# Goldfinger_Connector.net
KiCad netlist of a schematic drawn in Altium Designer
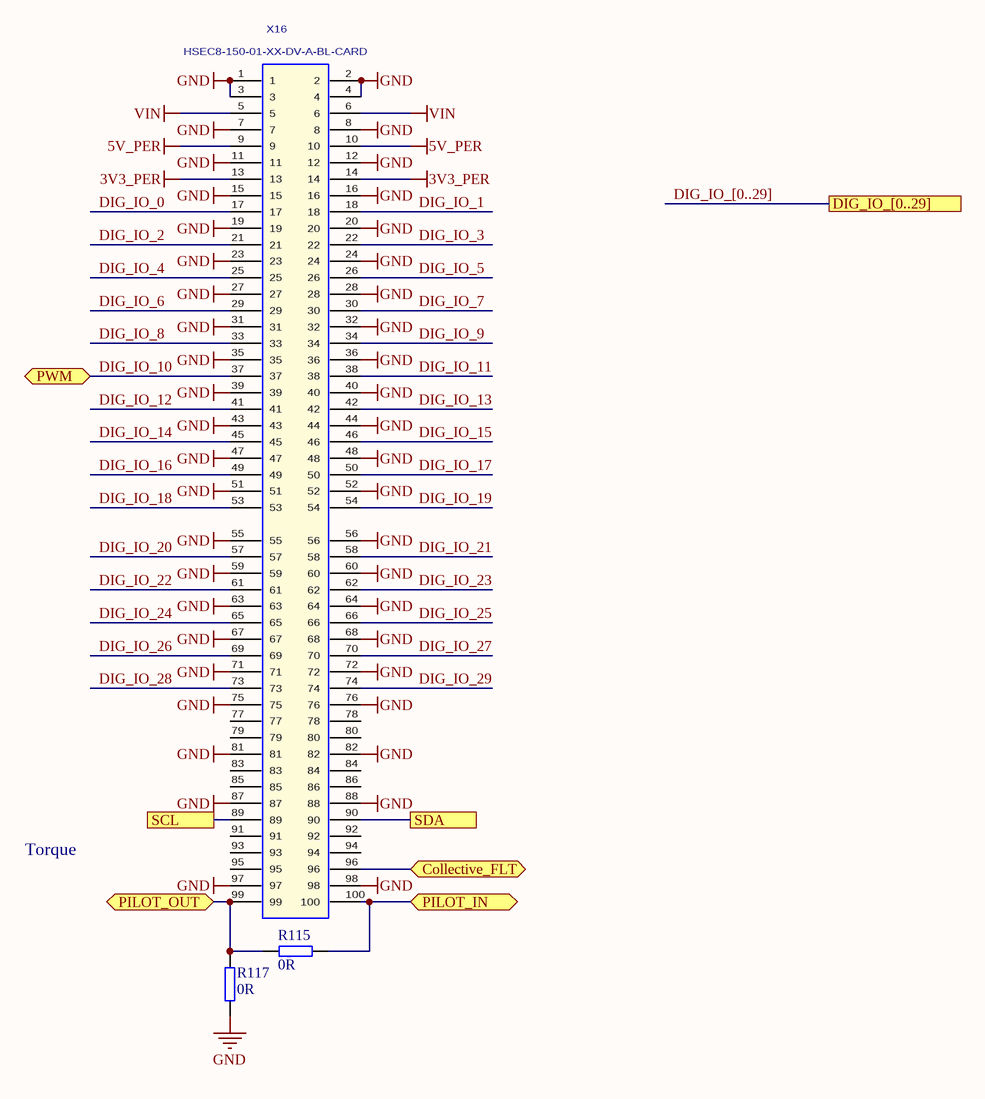
[diagram p0: Goldfinger_Connector.SchDoc]

(export (version "E")
  (design (tool "Eeschema 10.0.6"))
  (components
    (comp (ref "R115")
      (value "0R")
      (footprint "RESC1608X06N")
      (fields (field (name "MF") "Vishay") (field (name "MPN") "CRCW06030000Z0EAC"))
      (libsource (lib "UltraZohm_ADC") (part "R_0603"))
    )
    (comp (ref "R117")
      (value "0R")
      (footprint "RESC1608X06N")
      (fields (field (name "MF") "Vishay") (field (name "MPN") "CRCW06030000Z0EAC"))
      (libsource (lib "UltraZohm_ADC") (part "R_0603"))
    )
    (comp (ref "X16")
      (value "HSEC8-150-01-XX-DV-A-BL-CARD")
      (footprint "HSEC8-150-01-XX-DV-A-BL-CARD")
      (description "Mating Card Layout for HSEC8-150-01-XX-DV-A-BL")
      (fields (field (name "MANUFACTURER") "SAMTEC") (field (name "CREATED") "2018_04_23_AGeiger"))
      (libsource (lib "Samtec") (part "HSEC8-150-01-XX-DV-A-BL-CARD"))
    )
  )
  (nets
    (net (code "1") (name "/Collective_FLT") (class "Default")
      (node (ref "X16") (pin "96") (pinfunction "96_96") (pintype "passive"))
    )
    (net (code "2") (name "/DIG_IO_0") (class "Default")
      (node (ref "X16") (pin "17") (pinfunction "17_17") (pintype "passive"))
    )
    (net (code "3") (name "/DIG_IO_1") (class "Default")
      (node (ref "X16") (pin "18") (pinfunction "18_18") (pintype "passive"))
    )
    (net (code "4") (name "/DIG_IO_2") (class "Default")
      (node (ref "X16") (pin "21") (pinfunction "21_21") (pintype "passive"))
    )
    (net (code "5") (name "/DIG_IO_3") (class "Default")
      (node (ref "X16") (pin "22") (pinfunction "22_22") (pintype "passive"))
    )
    (net (code "6") (name "/DIG_IO_4") (class "Default")
      (node (ref "X16") (pin "25") (pinfunction "25_25") (pintype "passive"))
    )
    (net (code "7") (name "/DIG_IO_5") (class "Default")
      (node (ref "X16") (pin "26") (pinfunction "26_26") (pintype "passive"))
    )
    (net (code "8") (name "/DIG_IO_6") (class "Default")
      (node (ref "X16") (pin "29") (pinfunction "29_29") (pintype "passive"))
    )
    (net (code "9") (name "/DIG_IO_7") (class "Default")
      (node (ref "X16") (pin "30") (pinfunction "30_30") (pintype "passive"))
    )
    (net (code "10") (name "/DIG_IO_8") (class "Default")
      (node (ref "X16") (pin "33") (pinfunction "33_33") (pintype "passive"))
    )
    (net (code "11") (name "/DIG_IO_9") (class "Default")
      (node (ref "X16") (pin "34") (pinfunction "34_34") (pintype "passive"))
    )
    (net (code "12") (name "/DIG_IO_10") (class "Default")
      (node (ref "X16") (pin "37") (pinfunction "37_37") (pintype "passive"))
    )
    (net (code "13") (name "/DIG_IO_11") (class "Default")
      (node (ref "X16") (pin "38") (pinfunction "38_38") (pintype "passive"))
    )
    (net (code "14") (name "/DIG_IO_12") (class "Default")
      (node (ref "X16") (pin "41") (pinfunction "41_41") (pintype "passive"))
    )
    (net (code "15") (name "/DIG_IO_13") (class "Default")
      (node (ref "X16") (pin "42") (pinfunction "42_42") (pintype "passive"))
    )
    (net (code "16") (name "/DIG_IO_14") (class "Default")
      (node (ref "X16") (pin "45") (pinfunction "45_45") (pintype "passive"))
    )
    (net (code "17") (name "/DIG_IO_15") (class "Default")
      (node (ref "X16") (pin "46") (pinfunction "46_46") (pintype "passive"))
    )
    (net (code "18") (name "/DIG_IO_16") (class "Default")
      (node (ref "X16") (pin "49") (pinfunction "49_49") (pintype "passive"))
    )
    (net (code "19") (name "/DIG_IO_17") (class "Default")
      (node (ref "X16") (pin "50") (pinfunction "50_50") (pintype "passive"))
    )
    (net (code "20") (name "/DIG_IO_18") (class "Default")
      (node (ref "X16") (pin "53") (pinfunction "53_53") (pintype "passive"))
    )
    (net (code "21") (name "/DIG_IO_19") (class "Default")
      (node (ref "X16") (pin "54") (pinfunction "54_54") (pintype "passive"))
    )
    (net (code "22") (name "/DIG_IO_20") (class "Default")
      (node (ref "X16") (pin "57") (pinfunction "57_57") (pintype "passive"))
    )
    (net (code "23") (name "/DIG_IO_21") (class "Default")
      (node (ref "X16") (pin "58") (pinfunction "58_58") (pintype "passive"))
    )
    (net (code "24") (name "/DIG_IO_22") (class "Default")
      (node (ref "X16") (pin "61") (pinfunction "61_61") (pintype "passive"))
    )
    (net (code "25") (name "/DIG_IO_23") (class "Default")
      (node (ref "X16") (pin "62") (pinfunction "62_62") (pintype "passive"))
    )
    (net (code "26") (name "/DIG_IO_24") (class "Default")
      (node (ref "X16") (pin "65") (pinfunction "65_65") (pintype "passive"))
    )
    (net (code "27") (name "/DIG_IO_25") (class "Default")
      (node (ref "X16") (pin "66") (pinfunction "66_66") (pintype "passive"))
    )
    (net (code "28") (name "/DIG_IO_26") (class "Default")
      (node (ref "X16") (pin "69") (pinfunction "69_69") (pintype "passive"))
    )
    (net (code "29") (name "/DIG_IO_27") (class "Default")
      (node (ref "X16") (pin "70") (pinfunction "70_70") (pintype "passive"))
    )
    (net (code "30") (name "/DIG_IO_28") (class "Default")
      (node (ref "X16") (pin "73") (pinfunction "73_73") (pintype "passive"))
    )
    (net (code "31") (name "/DIG_IO_29") (class "Default")
      (node (ref "X16") (pin "74") (pinfunction "74_74") (pintype "passive"))
    )
    (net (code "33") (name "/PILOT_IN") (class "Default")
      (node (ref "R115") (pin "2") (pintype "passive"))
      (node (ref "X16") (pin "100") (pinfunction "100_100") (pintype "passive"))
    )
    (net (code "34") (name "/PILOT_OUT") (class "Default")
      (node (ref "R115") (pin "1") (pintype "passive"))
      (node (ref "R117") (pin "2") (pintype "passive"))
      (node (ref "X16") (pin "99") (pinfunction "99_99") (pintype "passive"))
    )
    (net (code "35") (name "/SCL") (class "Default")
      (node (ref "X16") (pin "89") (pinfunction "89_89") (pintype "passive"))
    )
    (net (code "36") (name "/SDA") (class "Default")
      (node (ref "X16") (pin "90") (pinfunction "90_90") (pintype "passive"))
    )
    (net (code "37") (name "3V3_PER") (class "Default")
      (node (ref "X16") (pin "13") (pinfunction "13_13") (pintype "passive"))
      (node (ref "X16") (pin "14") (pinfunction "14_14") (pintype "passive"))
    )
    (net (code "38") (name "5V_PER") (class "Default")
      (node (ref "X16") (pin "10") (pinfunction "10_10") (pintype "passive"))
      (node (ref "X16") (pin "9") (pinfunction "9_9") (pintype "passive"))
    )
    (net (code "39") (name "GND") (class "Default")
      (node (ref "R117") (pin "1") (pintype "passive"))
      (node (ref "X16") (pin "1") (pinfunction "1_1") (pintype "passive"))
      (node (ref "X16") (pin "11") (pinfunction "11_11") (pintype "passive"))
      (node (ref "X16") (pin "12") (pinfunction "12_12") (pintype "passive"))
      (node (ref "X16") (pin "15") (pinfunction "15_15") (pintype "passive"))
      (node (ref "X16") (pin "16") (pinfunction "16_16") (pintype "passive"))
      (node (ref "X16") (pin "19") (pinfunction "19_19") (pintype "passive"))
      (node (ref "X16") (pin "2") (pinfunction "2_2") (pintype "passive"))
      (node (ref "X16") (pin "20") (pinfunction "20_20") (pintype "passive"))
      (node (ref "X16") (pin "23") (pinfunction "23_23") (pintype "passive"))
      (node (ref "X16") (pin "24") (pinfunction "24_24") (pintype "passive"))
      (node (ref "X16") (pin "27") (pinfunction "27_27") (pintype "passive"))
      (node (ref "X16") (pin "28") (pinfunction "28_28") (pintype "passive"))
      (node (ref "X16") (pin "3") (pinfunction "3_3") (pintype "passive"))
      (node (ref "X16") (pin "31") (pinfunction "31_31") (pintype "passive"))
      (node (ref "X16") (pin "32") (pinfunction "32_32") (pintype "passive"))
      (node (ref "X16") (pin "35") (pinfunction "35_35") (pintype "passive"))
      (node (ref "X16") (pin "36") (pinfunction "36_36") (pintype "passive"))
      (node (ref "X16") (pin "39") (pinfunction "39_39") (pintype "passive"))
      (node (ref "X16") (pin "4") (pinfunction "4_4") (pintype "passive"))
      (node (ref "X16") (pin "40") (pinfunction "40_40") (pintype "passive"))
      (node (ref "X16") (pin "43") (pinfunction "43_43") (pintype "passive"))
      (node (ref "X16") (pin "44") (pinfunction "44_44") (pintype "passive"))
      (node (ref "X16") (pin "47") (pinfunction "47_47") (pintype "passive"))
      (node (ref "X16") (pin "48") (pinfunction "48_48") (pintype "passive"))
      (node (ref "X16") (pin "51") (pinfunction "51_51") (pintype "passive"))
      (node (ref "X16") (pin "52") (pinfunction "52_52") (pintype "passive"))
      (node (ref "X16") (pin "55") (pinfunction "55_55") (pintype "passive"))
      (node (ref "X16") (pin "56") (pinfunction "56_56") (pintype "passive"))
      (node (ref "X16") (pin "59") (pinfunction "59_59") (pintype "passive"))
      (node (ref "X16") (pin "60") (pinfunction "60_60") (pintype "passive"))
      (node (ref "X16") (pin "63") (pinfunction "63_63") (pintype "passive"))
      (node (ref "X16") (pin "64") (pinfunction "64_64") (pintype "passive"))
      (node (ref "X16") (pin "67") (pinfunction "67_67") (pintype "passive"))
      (node (ref "X16") (pin "68") (pinfunction "68_68") (pintype "passive"))
      (node (ref "X16") (pin "7") (pinfunction "7_7") (pintype "passive"))
      (node (ref "X16") (pin "71") (pinfunction "71_71") (pintype "passive"))
      (node (ref "X16") (pin "72") (pinfunction "72_72") (pintype "passive"))
      (node (ref "X16") (pin "75") (pinfunction "75_75") (pintype "passive"))
      (node (ref "X16") (pin "76") (pinfunction "76_76") (pintype "passive"))
      (node (ref "X16") (pin "8") (pinfunction "8_8") (pintype "passive"))
      (node (ref "X16") (pin "81") (pinfunction "81_81") (pintype "passive"))
      (node (ref "X16") (pin "82") (pinfunction "82_82") (pintype "passive"))
      (node (ref "X16") (pin "87") (pinfunction "87_87") (pintype "passive"))
      (node (ref "X16") (pin "88") (pinfunction "88_88") (pintype "passive"))
      (node (ref "X16") (pin "97") (pinfunction "97_97") (pintype "passive"))
      (node (ref "X16") (pin "98") (pinfunction "98_98") (pintype "passive"))
    )
    (net (code "40") (name "VIN") (class "Default")
      (node (ref "X16") (pin "5") (pinfunction "5_5") (pintype "passive"))
      (node (ref "X16") (pin "6") (pinfunction "6_6") (pintype "passive"))
    )
    (net (code "41") (name "unconnected-(X16-Pad77)") (class "Default")
      (node (ref "X16") (pin "77") (pinfunction "77_77") (pintype "passive"))
    )
    (net (code "42") (name "unconnected-(X16-Pad78)") (class "Default")
      (node (ref "X16") (pin "78") (pinfunction "78_78") (pintype "passive"))
    )
    (net (code "43") (name "unconnected-(X16-Pad79)") (class "Default")
      (node (ref "X16") (pin "79") (pinfunction "79_79") (pintype "passive"))
    )
    (net (code "44") (name "unconnected-(X16-Pad80)") (class "Default")
      (node (ref "X16") (pin "80") (pinfunction "80_80") (pintype "passive"))
    )
    (net (code "45") (name "unconnected-(X16-Pad83)") (class "Default")
      (node (ref "X16") (pin "83") (pinfunction "83_83") (pintype "passive"))
    )
    (net (code "46") (name "unconnected-(X16-Pad84)") (class "Default")
      (node (ref "X16") (pin "84") (pinfunction "84_84") (pintype "passive"))
    )
    (net (code "47") (name "unconnected-(X16-Pad85)") (class "Default")
      (node (ref "X16") (pin "85") (pinfunction "85_85") (pintype "passive"))
    )
    (net (code "48") (name "unconnected-(X16-Pad86)") (class "Default")
      (node (ref "X16") (pin "86") (pinfunction "86_86") (pintype "passive"))
    )
    (net (code "49") (name "unconnected-(X16-Pad91)") (class "Default")
      (node (ref "X16") (pin "91") (pinfunction "91_91") (pintype "passive"))
    )
    (net (code "50") (name "unconnected-(X16-Pad92)") (class "Default")
      (node (ref "X16") (pin "92") (pinfunction "92_92") (pintype "passive"))
    )
    (net (code "51") (name "unconnected-(X16-Pad93)") (class "Default")
      (node (ref "X16") (pin "93") (pinfunction "93_93") (pintype "passive"))
    )
    (net (code "52") (name "unconnected-(X16-Pad94)") (class "Default")
      (node (ref "X16") (pin "94") (pinfunction "94_94") (pintype "passive"))
    )
    (net (code "53") (name "unconnected-(X16-Pad95)") (class "Default")
      (node (ref "X16") (pin "95") (pinfunction "95_95") (pintype "passive"))
    )
  )
)
